# Sheet1.net
KiCad netlist of a schematic drawn in Altium Designer
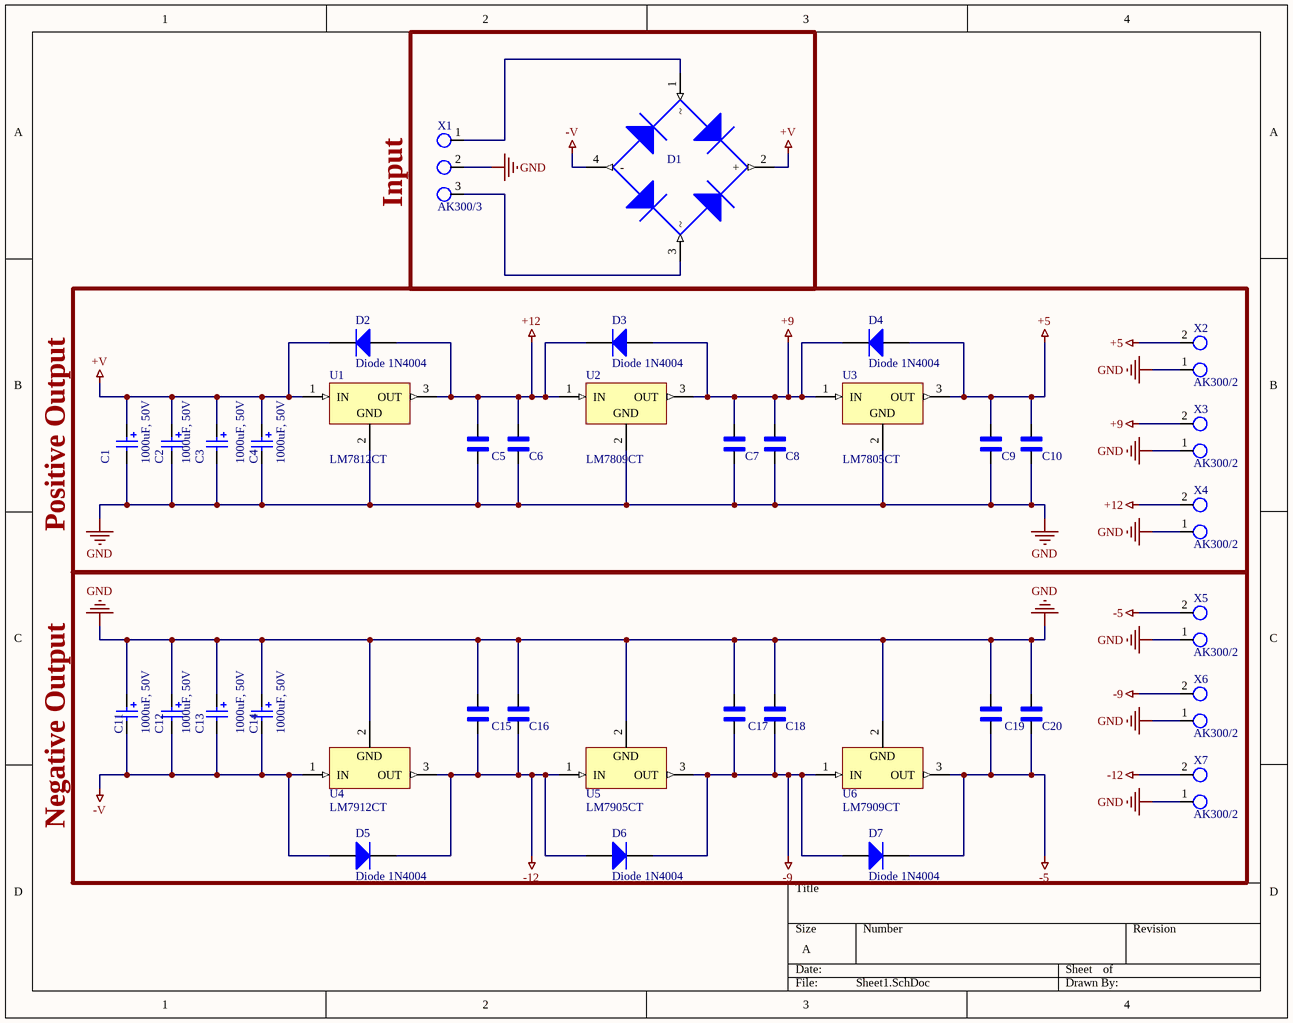
[diagram p0: Sheet1.SchDoc]

(export (version "E")
  (design (tool "Eeschema 10.0.6"))
  (components
    (comp (ref "C1")
      (value "1000uF, 50V")
      (footprint "WCAP-ATG8_D13H25")
      (description "WCAP-ATG8 Aluminum Electrolytic Capacitor, Radial, THT, D13xH25, 1000uF, 50V")
      (fields
        (field (name "MANUFACTURER PART NUMBER") "860010678024")
        (field (name "MANUFACTURER") "Wurth Elektronik")
      )
      (libsource (lib "Schlib1") (part "860010678024"))
    )
    (comp (ref "C2")
      (value "1000uF, 50V")
      (footprint "WCAP-ATG8_D13H25")
      (description "WCAP-ATG8 Aluminum Electrolytic Capacitor, Radial, THT, D13xH25, 1000uF, 50V")
      (fields
        (field (name "MANUFACTURER PART NUMBER") "860010678024")
        (field (name "MANUFACTURER") "Wurth Elektronik")
      )
      (libsource (lib "Schlib1") (part "860010678024"))
    )
    (comp (ref "C3")
      (value "1000uF, 50V")
      (footprint "WCAP-ATG8_D13H25")
      (description "WCAP-ATG8 Aluminum Electrolytic Capacitor, Radial, THT, D13xH25, 1000uF, 50V")
      (fields
        (field (name "MANUFACTURER PART NUMBER") "860010678024")
        (field (name "MANUFACTURER") "Wurth Elektronik")
      )
      (libsource (lib "Schlib1") (part "860010678024"))
    )
    (comp (ref "C4")
      (value "1000uF, 50V")
      (footprint "WCAP-ATG8_D13H25")
      (description "WCAP-ATG8 Aluminum Electrolytic Capacitor, Radial, THT, D13xH25, 1000uF, 50V")
      (fields
        (field (name "MANUFACTURER PART NUMBER") "860010678024")
        (field (name "MANUFACTURER") "Wurth Elektronik")
      )
      (libsource (lib "Schlib1") (part "860010678024"))
    )
    (comp (ref "C5")
      (value "RDE5C2A220J0M1H03A")
      (footprint "CAP_RDE5C2A220J0M1H03A")
      (description "Lead Capacitor C0G_EIA_ with Capacitance: 22pF and Rated Voltage: 100Vdc")
      (fields (field (name "MF") "Murata"))
      (libsource (lib "Schlib1") (part "RDE5C2A220J0M1H03A"))
    )
    (comp (ref "C6")
      (value "RDE5C2A220J0M1H03A")
      (footprint "CAP_RDE5C2A220J0M1H03A")
      (description "Lead Capacitor C0G_EIA_ with Capacitance: 22pF and Rated Voltage: 100Vdc")
      (fields (field (name "MF") "Murata"))
      (libsource (lib "Schlib1") (part "RDE5C2A220J0M1H03A"))
    )
    (comp (ref "C7")
      (value "RDE5C2A220J0M1H03A")
      (footprint "CAP_RDE5C2A220J0M1H03A")
      (description "Lead Capacitor C0G_EIA_ with Capacitance: 22pF and Rated Voltage: 100Vdc")
      (fields (field (name "MF") "Murata"))
      (libsource (lib "Schlib1") (part "RDE5C2A220J0M1H03A"))
    )
    (comp (ref "C8")
      (value "RDE5C2A220J0M1H03A")
      (footprint "CAP_RDE5C2A220J0M1H03A")
      (description "Lead Capacitor C0G_EIA_ with Capacitance: 22pF and Rated Voltage: 100Vdc")
      (fields (field (name "MF") "Murata"))
      (libsource (lib "Schlib1") (part "RDE5C2A220J0M1H03A"))
    )
    (comp (ref "C9")
      (value "RDE5C2A220J0M1H03A")
      (footprint "CAP_RDE5C2A220J0M1H03A")
      (description "Lead Capacitor C0G_EIA_ with Capacitance: 22pF and Rated Voltage: 100Vdc")
      (fields (field (name "MF") "Murata"))
      (libsource (lib "Schlib1") (part "RDE5C2A220J0M1H03A"))
    )
    (comp (ref "C10")
      (value "RDE5C2A220J0M1H03A")
      (footprint "CAP_RDE5C2A220J0M1H03A")
      (description "Lead Capacitor C0G_EIA_ with Capacitance: 22pF and Rated Voltage: 100Vdc")
      (fields (field (name "MF") "Murata"))
      (libsource (lib "Schlib1") (part "RDE5C2A220J0M1H03A"))
    )
    (comp (ref "C11")
      (value "1000uF, 50V")
      (footprint "WCAP-ATG8_D13H25")
      (description "WCAP-ATG8 Aluminum Electrolytic Capacitor, Radial, THT, D13xH25, 1000uF, 50V")
      (fields
        (field (name "MANUFACTURER PART NUMBER") "860010678024")
        (field (name "MANUFACTURER") "Wurth Elektronik")
      )
      (libsource (lib "Schlib1") (part "860010678024"))
    )
    (comp (ref "C12")
      (value "1000uF, 50V")
      (footprint "WCAP-ATG8_D13H25")
      (description "WCAP-ATG8 Aluminum Electrolytic Capacitor, Radial, THT, D13xH25, 1000uF, 50V")
      (fields
        (field (name "MANUFACTURER PART NUMBER") "860010678024")
        (field (name "MANUFACTURER") "Wurth Elektronik")
      )
      (libsource (lib "Schlib1") (part "860010678024"))
    )
    (comp (ref "C13")
      (value "1000uF, 50V")
      (footprint "WCAP-ATG8_D13H25")
      (description "WCAP-ATG8 Aluminum Electrolytic Capacitor, Radial, THT, D13xH25, 1000uF, 50V")
      (fields
        (field (name "MANUFACTURER PART NUMBER") "860010678024")
        (field (name "MANUFACTURER") "Wurth Elektronik")
      )
      (libsource (lib "Schlib1") (part "860010678024"))
    )
    (comp (ref "C14")
      (value "1000uF, 50V")
      (footprint "WCAP-ATG8_D13H25")
      (description "WCAP-ATG8 Aluminum Electrolytic Capacitor, Radial, THT, D13xH25, 1000uF, 50V")
      (fields
        (field (name "MANUFACTURER PART NUMBER") "860010678024")
        (field (name "MANUFACTURER") "Wurth Elektronik")
      )
      (libsource (lib "Schlib1") (part "860010678024"))
    )
    (comp (ref "C15")
      (value "RDE5C2A220J0M1H03A")
      (footprint "CAP_RDE5C2A220J0M1H03A")
      (description "Lead Capacitor C0G_EIA_ with Capacitance: 22pF and Rated Voltage: 100Vdc")
      (fields (field (name "MF") "Murata"))
      (libsource (lib "Schlib1") (part "RDE5C2A220J0M1H03A"))
    )
    (comp (ref "C16")
      (value "RDE5C2A220J0M1H03A")
      (footprint "CAP_RDE5C2A220J0M1H03A")
      (description "Lead Capacitor C0G_EIA_ with Capacitance: 22pF and Rated Voltage: 100Vdc")
      (fields (field (name "MF") "Murata"))
      (libsource (lib "Schlib1") (part "RDE5C2A220J0M1H03A"))
    )
    (comp (ref "C17")
      (value "RDE5C2A220J0M1H03A")
      (footprint "CAP_RDE5C2A220J0M1H03A")
      (description "Lead Capacitor C0G_EIA_ with Capacitance: 22pF and Rated Voltage: 100Vdc")
      (fields (field (name "MF") "Murata"))
      (libsource (lib "Schlib1") (part "RDE5C2A220J0M1H03A"))
    )
    (comp (ref "C18")
      (value "RDE5C2A220J0M1H03A")
      (footprint "CAP_RDE5C2A220J0M1H03A")
      (description "Lead Capacitor C0G_EIA_ with Capacitance: 22pF and Rated Voltage: 100Vdc")
      (fields (field (name "MF") "Murata"))
      (libsource (lib "Schlib1") (part "RDE5C2A220J0M1H03A"))
    )
    (comp (ref "C19")
      (value "RDE5C2A220J0M1H03A")
      (footprint "CAP_RDE5C2A220J0M1H03A")
      (description "Lead Capacitor C0G_EIA_ with Capacitance: 22pF and Rated Voltage: 100Vdc")
      (fields (field (name "MF") "Murata"))
      (libsource (lib "Schlib1") (part "RDE5C2A220J0M1H03A"))
    )
    (comp (ref "C20")
      (value "RDE5C2A220J0M1H03A")
      (footprint "CAP_RDE5C2A220J0M1H03A")
      (description "Lead Capacitor C0G_EIA_ with Capacitance: 22pF and Rated Voltage: 100Vdc")
      (fields (field (name "MF") "Murata"))
      (libsource (lib "Schlib1") (part "RDE5C2A220J0M1H03A"))
    )
    (comp (ref "D1") (value "2W10G") (footprint "2W10G") (libsource (lib "Schlib1") (part "2W10G")))
    (comp (ref "D2")
      (value "Diode 1N4004")
      (footprint "DO-41")
      (description "1 Amp General Purpose Rectifier")
      (fields (field (name "PUBLISHER") "Altium Limited"))
      (libsource (lib "Miscellaneous Devices") (part "Diode 1N4004"))
    )
    (comp (ref "D3")
      (value "Diode 1N4004")
      (footprint "DO-41")
      (description "1 Amp General Purpose Rectifier")
      (fields (field (name "PUBLISHER") "Altium Limited"))
      (libsource (lib "Miscellaneous Devices") (part "Diode 1N4004"))
    )
    (comp (ref "D4")
      (value "Diode 1N4004")
      (footprint "DO-41")
      (description "1 Amp General Purpose Rectifier")
      (fields (field (name "PUBLISHER") "Altium Limited"))
      (libsource (lib "Miscellaneous Devices") (part "Diode 1N4004"))
    )
    (comp (ref "D5")
      (value "Diode 1N4004")
      (footprint "DO-41")
      (description "1 Amp General Purpose Rectifier")
      (fields (field (name "PUBLISHER") "Altium Limited"))
      (libsource (lib "Miscellaneous Devices") (part "Diode 1N4004"))
    )
    (comp (ref "D6")
      (value "Diode 1N4004")
      (footprint "DO-41")
      (description "1 Amp General Purpose Rectifier")
      (fields (field (name "PUBLISHER") "Altium Limited"))
      (libsource (lib "Miscellaneous Devices") (part "Diode 1N4004"))
    )
    (comp (ref "D7")
      (value "Diode 1N4004")
      (footprint "DO-41")
      (description "1 Amp General Purpose Rectifier")
      (fields (field (name "PUBLISHER") "Altium Limited"))
      (libsource (lib "Miscellaneous Devices") (part "Diode 1N4004"))
    )
    (comp (ref "U1")
      (value "LM7812CT")
      (footprint "TO-220-P")
      (fields (field (name "MANUFACTURER") "FairchildSemiconductor"))
      (libsource (lib "Schlib1") (part "7812"))
    )
    (comp (ref "U2")
      (value "LM7809CT")
      (footprint "TO-220-P")
      (fields (field (name "MANUFACTURER") "FairchildSemiconductor"))
      (libsource (lib "Schlib1") (part "7809"))
    )
    (comp (ref "U3")
      (value "LM7805CT")
      (footprint "TO-220-P")
      (description "Positive Voltage Regulator, 5 V, 1 A, -40 to 125 degC, 3-Pin TO-220, RoHS, Tube")
      (fields (field (name "MANUFACTURER") "FairchildSemiconductor"))
      (libsource (lib "Schlib1") (part "7805"))
    )
    (comp (ref "U4")
      (value "LM7912CT")
      (footprint "TO-220-N")
      (fields (field (name "MANUFACTURER") "FairchildSemiconductor"))
      (libsource (lib "Schlib1") (part "7912"))
    )
    (comp (ref "U5")
      (value "LM7905CT")
      (footprint "TO-220-N")
      (description "Negative Voltage Regulator, 5 V, 1 A, -40 to 125 degC, 3-Pin TO-220, RoHS, Tube")
      (fields (field (name "MANUFACTURER") "FairchildSemiconductor"))
      (libsource (lib "Schlib1") (part "7905"))
    )
    (comp (ref "U6")
      (value "LM7909CT")
      (footprint "TO-220-N")
      (fields (field (name "MANUFACTURER") "FairchildSemiconductor"))
      (libsource (lib "Schlib1") (part "7909"))
    )
    (comp (ref "X1")
      (value "AK300/3")
      (footprint "AK300/3")
      (fields (field (name "MF") "Altech"))
      (libsource (lib "Schlib1") (part "AK300/3"))
    )
    (comp (ref "X2")
      (value "AK300/2")
      (footprint "AK300/2")
      (fields (field (name "MP") "AK300/3") (field (name "MF") "Altech"))
      (libsource (lib "Schlib1") (part "AK300/2"))
    )
    (comp (ref "X3")
      (value "AK300/2")
      (footprint "AK300/2")
      (fields (field (name "MP") "AK300/3") (field (name "MF") "Altech"))
      (libsource (lib "Schlib1") (part "AK300/2"))
    )
    (comp (ref "X4")
      (value "AK300/2")
      (footprint "AK300/2")
      (fields (field (name "MP") "AK300/3") (field (name "MF") "Altech"))
      (libsource (lib "Schlib1") (part "AK300/2"))
    )
    (comp (ref "X5")
      (value "AK300/2")
      (footprint "AK300/2")
      (fields (field (name "MP") "AK300/3") (field (name "MF") "Altech"))
      (libsource (lib "Schlib1") (part "AK300/2"))
    )
    (comp (ref "X6")
      (value "AK300/2")
      (footprint "AK300/2")
      (fields (field (name "MP") "AK300/3") (field (name "MF") "Altech"))
      (libsource (lib "Schlib1") (part "AK300/2"))
    )
    (comp (ref "X7")
      (value "AK300/2")
      (footprint "AK300/2")
      (fields (field (name "MP") "AK300/3") (field (name "MF") "Altech"))
      (libsource (lib "Schlib1") (part "AK300/2"))
    )
  )
  (nets
    (net (code "1") (name "+5") (class "Default")
      (node (ref "C10") (pin "2") (pinfunction "2_2") (pintype "passive"))
      (node (ref "C9") (pin "2") (pinfunction "2_2") (pintype "passive"))
      (node (ref "D4") (pin "1") (pinfunction "A_1") (pintype "passive"))
      (node (ref "U3") (pin "3") (pinfunction "OUT_3") (pintype "output"))
      (node (ref "X2") (pin "2") (pinfunction "KL_2") (pintype "passive"))
    )
    (net (code "2") (name "+9") (class "Default")
      (node (ref "C7") (pin "2") (pinfunction "2_2") (pintype "passive"))
      (node (ref "C8") (pin "2") (pinfunction "2_2") (pintype "passive"))
      (node (ref "D3") (pin "1") (pinfunction "A_1") (pintype "passive"))
      (node (ref "D4") (pin "2") (pinfunction "K_2") (pintype "passive"))
      (node (ref "U2") (pin "3") (pinfunction "OUT_3") (pintype "output"))
      (node (ref "U3") (pin "1") (pinfunction "IN_1") (pintype "input"))
      (node (ref "X3") (pin "2") (pinfunction "KL_2") (pintype "passive"))
    )
    (net (code "3") (name "+12") (class "Default")
      (node (ref "C5") (pin "2") (pinfunction "2_2") (pintype "passive"))
      (node (ref "C6") (pin "2") (pinfunction "2_2") (pintype "passive"))
      (node (ref "D2") (pin "1") (pinfunction "A_1") (pintype "passive"))
      (node (ref "D3") (pin "2") (pinfunction "K_2") (pintype "passive"))
      (node (ref "U1") (pin "3") (pinfunction "OUT_3") (pintype "output"))
      (node (ref "U2") (pin "1") (pinfunction "IN_1") (pintype "input"))
      (node (ref "X4") (pin "2") (pinfunction "KL_2") (pintype "passive"))
    )
    (net (code "4") (name "+V") (class "Default")
      (node (ref "C1") (pin "1") (pinfunction "P_1") (pintype "passive"))
      (node (ref "C2") (pin "1") (pinfunction "P_1") (pintype "passive"))
      (node (ref "C3") (pin "1") (pinfunction "P_1") (pintype "passive"))
      (node (ref "C4") (pin "1") (pinfunction "P_1") (pintype "passive"))
      (node (ref "D1") (pin "2") (pinfunction "+_2") (pintype "output"))
      (node (ref "D2") (pin "2") (pinfunction "K_2") (pintype "passive"))
      (node (ref "U1") (pin "1") (pinfunction "IN_1") (pintype "input"))
    )
    (net (code "5") (name "-5") (class "Default")
      (node (ref "C19") (pin "1") (pinfunction "1_1") (pintype "passive"))
      (node (ref "C20") (pin "1") (pinfunction "1_1") (pintype "passive"))
      (node (ref "D7") (pin "2") (pinfunction "K_2") (pintype "passive"))
      (node (ref "U6") (pin "3") (pinfunction "OUT_3") (pintype "output"))
      (node (ref "X5") (pin "2") (pinfunction "KL_2") (pintype "passive"))
    )
    (net (code "6") (name "-9") (class "Default")
      (node (ref "C17") (pin "1") (pinfunction "1_1") (pintype "passive"))
      (node (ref "C18") (pin "1") (pinfunction "1_1") (pintype "passive"))
      (node (ref "D6") (pin "2") (pinfunction "K_2") (pintype "passive"))
      (node (ref "D7") (pin "1") (pinfunction "A_1") (pintype "passive"))
      (node (ref "U5") (pin "3") (pinfunction "OUT_3") (pintype "output"))
      (node (ref "U6") (pin "1") (pinfunction "IN_1") (pintype "input"))
      (node (ref "X6") (pin "2") (pinfunction "KL_2") (pintype "passive"))
    )
    (net (code "7") (name "-12") (class "Default")
      (node (ref "C15") (pin "1") (pinfunction "1_1") (pintype "passive"))
      (node (ref "C16") (pin "1") (pinfunction "1_1") (pintype "passive"))
      (node (ref "D5") (pin "2") (pinfunction "K_2") (pintype "passive"))
      (node (ref "D6") (pin "1") (pinfunction "A_1") (pintype "passive"))
      (node (ref "U4") (pin "3") (pinfunction "OUT_3") (pintype "output"))
      (node (ref "U5") (pin "1") (pinfunction "IN_1") (pintype "input"))
      (node (ref "X7") (pin "2") (pinfunction "KL_2") (pintype "passive"))
    )
    (net (code "8") (name "-V") (class "Default")
      (node (ref "C11") (pin "2") (pinfunction "N_2") (pintype "passive"))
      (node (ref "C12") (pin "2") (pinfunction "N_2") (pintype "passive"))
      (node (ref "C13") (pin "2") (pinfunction "N_2") (pintype "passive"))
      (node (ref "C14") (pin "2") (pinfunction "N_2") (pintype "passive"))
      (node (ref "D1") (pin "4") (pinfunction "-_4") (pintype "output"))
      (node (ref "D5") (pin "1") (pinfunction "A_1") (pintype "passive"))
      (node (ref "U4") (pin "1") (pinfunction "IN_1") (pintype "input"))
    )
    (net (code "9") (name "GND") (class "Default")
      (node (ref "C1") (pin "2") (pinfunction "N_2") (pintype "passive"))
      (node (ref "C10") (pin "1") (pinfunction "1_1") (pintype "passive"))
      (node (ref "C11") (pin "1") (pinfunction "P_1") (pintype "passive"))
      (node (ref "C12") (pin "1") (pinfunction "P_1") (pintype "passive"))
      (node (ref "C13") (pin "1") (pinfunction "P_1") (pintype "passive"))
      (node (ref "C14") (pin "1") (pinfunction "P_1") (pintype "passive"))
      (node (ref "C15") (pin "2") (pinfunction "2_2") (pintype "passive"))
      (node (ref "C16") (pin "2") (pinfunction "2_2") (pintype "passive"))
      (node (ref "C17") (pin "2") (pinfunction "2_2") (pintype "passive"))
      (node (ref "C18") (pin "2") (pinfunction "2_2") (pintype "passive"))
      (node (ref "C19") (pin "2") (pinfunction "2_2") (pintype "passive"))
      (node (ref "C2") (pin "2") (pinfunction "N_2") (pintype "passive"))
      (node (ref "C20") (pin "2") (pinfunction "2_2") (pintype "passive"))
      (node (ref "C3") (pin "2") (pinfunction "N_2") (pintype "passive"))
      (node (ref "C4") (pin "2") (pinfunction "N_2") (pintype "passive"))
      (node (ref "C5") (pin "1") (pinfunction "1_1") (pintype "passive"))
      (node (ref "C6") (pin "1") (pinfunction "1_1") (pintype "passive"))
      (node (ref "C7") (pin "1") (pinfunction "1_1") (pintype "passive"))
      (node (ref "C8") (pin "1") (pinfunction "1_1") (pintype "passive"))
      (node (ref "C9") (pin "1") (pinfunction "1_1") (pintype "passive"))
      (node (ref "U1") (pin "2") (pinfunction "GND_2") (pintype "power_in"))
      (node (ref "U2") (pin "2") (pinfunction "GND_2") (pintype "power_in"))
      (node (ref "U3") (pin "2") (pinfunction "GND_2") (pintype "power_in"))
      (node (ref "U4") (pin "2") (pinfunction "GND_2") (pintype "power_in"))
      (node (ref "U5") (pin "2") (pinfunction "GND_2") (pintype "power_in"))
      (node (ref "U6") (pin "2") (pinfunction "GND_2") (pintype "power_in"))
      (node (ref "X1") (pin "2") (pinfunction "KL_2") (pintype "passive"))
      (node (ref "X2") (pin "1") (pinfunction "KL_1") (pintype "passive"))
      (node (ref "X3") (pin "1") (pinfunction "KL_1") (pintype "passive"))
      (node (ref "X4") (pin "1") (pinfunction "KL_1") (pintype "passive"))
      (node (ref "X5") (pin "1") (pinfunction "KL_1") (pintype "passive"))
      (node (ref "X6") (pin "1") (pinfunction "KL_1") (pintype "passive"))
      (node (ref "X7") (pin "1") (pinfunction "KL_1") (pintype "passive"))
    )
    (net (code "10") (name "Net-(D1-~-Pad1)") (class "Default")
      (node (ref "D1") (pin "1") (pinfunction "~_1") (pintype "input"))
      (node (ref "X1") (pin "1") (pinfunction "KL_1") (pintype "passive"))
    )
    (net (code "11") (name "Net-(D1-~-Pad3)") (class "Default")
      (node (ref "D1") (pin "3") (pinfunction "~_3") (pintype "input"))
      (node (ref "X1") (pin "3") (pinfunction "KL_3") (pintype "passive"))
    )
  )
)
